# Rail_Splitter.net
KiCad netlist of a schematic drawn in Altium Designer
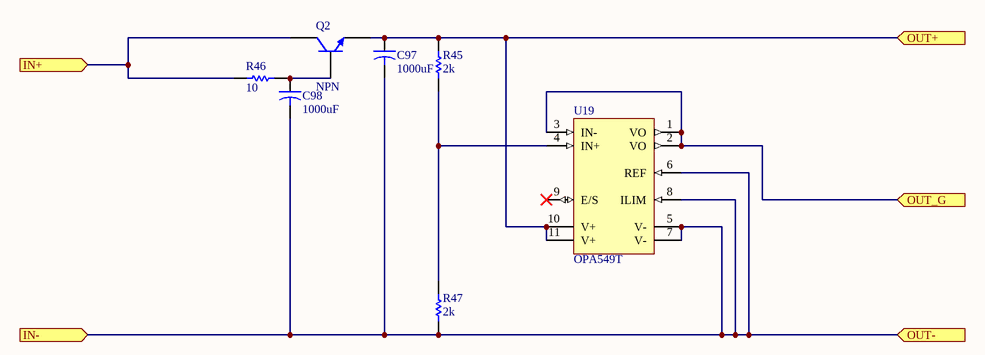
[diagram p0: Rail_Splitter.SchDoc]

(export (version "E")
  (design (tool "Eeschema 10.0.6"))
  (components
    (comp (ref "C97")
      (value "1000uF")
      (footprint "UVR1V102MHD1TO")
      (description "Capacitor, 100uF NICHICON")
      (libsource (lib "Arturo_Approved") (part "UVR1V102MHD1TO"))
    )
    (comp (ref "C98")
      (value "1000uF")
      (footprint "UVR1V102MHD1TO")
      (description "Capacitor, 100uF NICHICON")
      (libsource (lib "Arturo_Approved") (part "UVR1V102MHD1TO"))
    )
    (comp (ref "Q2")
      (value "NPN")
      (footprint "TO-220-3")
      (description "NPN Bipolar Transistor")
      (fields (field (name "PUBLISHER") "Altium Limited"))
      (libsource (lib "Miscellaneous Devices") (part "NPN"))
    )
    (comp (ref "R45")
      (value "2k")
      (footprint "STD_0805_R")
      (description "17.8k")
      (libsource (lib "Arturo_Approved") (part "RC0805FR-0717K8L"))
    )
    (comp (ref "R46")
      (value "10")
      (footprint "2512_SMD")
      (description "10 ohm 0805")
      (libsource (lib "Arturo_Approved") (part "RNCF0805DTE10R0"))
    )
    (comp (ref "R47")
      (value "2k")
      (footprint "STD_0805_R")
      (description "17.8k")
      (libsource (lib "Arturo_Approved") (part "RC0805FR-0717K8L"))
    )
    (comp (ref "U19")
      (value "OPA549T")
      (footprint "KV0011A")
      (fields (field (name "MANUFACTURER") "Texas Instruments"))
      (libsource (lib "Altium Content Vault") (part "TI-OPA549-11"))
    )
  )
  (nets
    (net (code "1") (name "/IN+") (class "Default")
      (node (ref "Q2") (pin "1") (pinfunction "C_1") (pintype "passive"))
      (node (ref "R46") (pin "1") (pinfunction "1_1") (pintype "passive"))
    )
    (net (code "2") (name "/IN-") (class "Default")
      (node (ref "C97") (pin "2") (pinfunction "2_2") (pintype "passive"))
      (node (ref "C98") (pin "2") (pinfunction "2_2") (pintype "passive"))
      (node (ref "R47") (pin "1") (pinfunction "1_1") (pintype "passive"))
      (node (ref "U19") (pin "5") (pinfunction "V-_5") (pintype "power_in"))
      (node (ref "U19") (pin "6") (pinfunction "REF_6") (pintype "input"))
      (node (ref "U19") (pin "7") (pinfunction "V-_7") (pintype "power_in"))
      (node (ref "U19") (pin "8") (pinfunction "ILIM_8") (pintype "input"))
    )
    (net (code "3") (name "/OUT+") (class "Default")
      (node (ref "C97") (pin "1") (pinfunction "1_1") (pintype "passive"))
      (node (ref "Q2") (pin "3") (pinfunction "E_3") (pintype "passive"))
      (node (ref "R45") (pin "2") (pinfunction "2_2") (pintype "passive"))
      (node (ref "U19") (pin "10") (pinfunction "V+_10") (pintype "power_in"))
      (node (ref "U19") (pin "11") (pinfunction "V+_11") (pintype "power_in"))
    )
    (net (code "4") (name "/OUT_G") (class "Default")
      (node (ref "U19") (pin "1") (pinfunction "VO_1") (pintype "output"))
      (node (ref "U19") (pin "2") (pinfunction "VO_2") (pintype "output"))
      (node (ref "U19") (pin "3") (pinfunction "IN-_3") (pintype "input"))
    )
    (net (code "5") (name "Net-(Q2-B)") (class "Default")
      (node (ref "C98") (pin "1") (pinfunction "1_1") (pintype "passive"))
      (node (ref "Q2") (pin "2") (pinfunction "B_2") (pintype "passive"))
      (node (ref "R46") (pin "2") (pinfunction "2_2") (pintype "passive"))
    )
    (net (code "6") (name "Net-(U19-IN+)") (class "Default")
      (node (ref "R45") (pin "1") (pinfunction "1_1") (pintype "passive"))
      (node (ref "R47") (pin "2") (pinfunction "2_2") (pintype "passive"))
      (node (ref "U19") (pin "4") (pinfunction "IN+_4") (pintype "input"))
    )
    (net (code "7") (name "unconnected-(U19-E{slash}S-Pad9)") (class "Default")
      (node (ref "U19") (pin "9") (pinfunction "E/S_9") (pintype "bidirectional+no_connect"))
    )
  )
)
